# v1.net
KiCad netlist of a schematic drawn in EAGLE
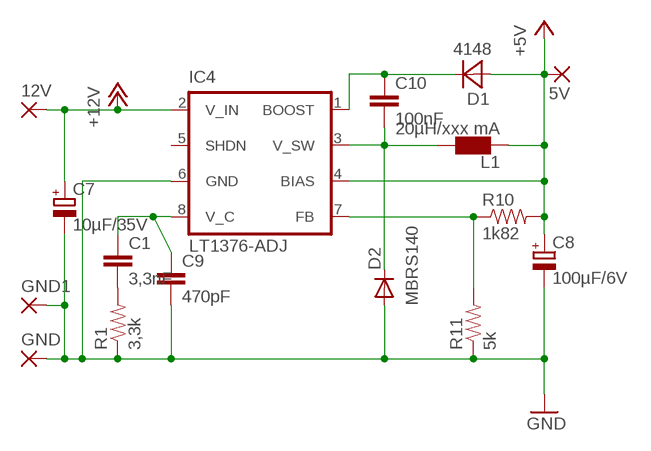
[diagram p0: schematic, sheet 1]
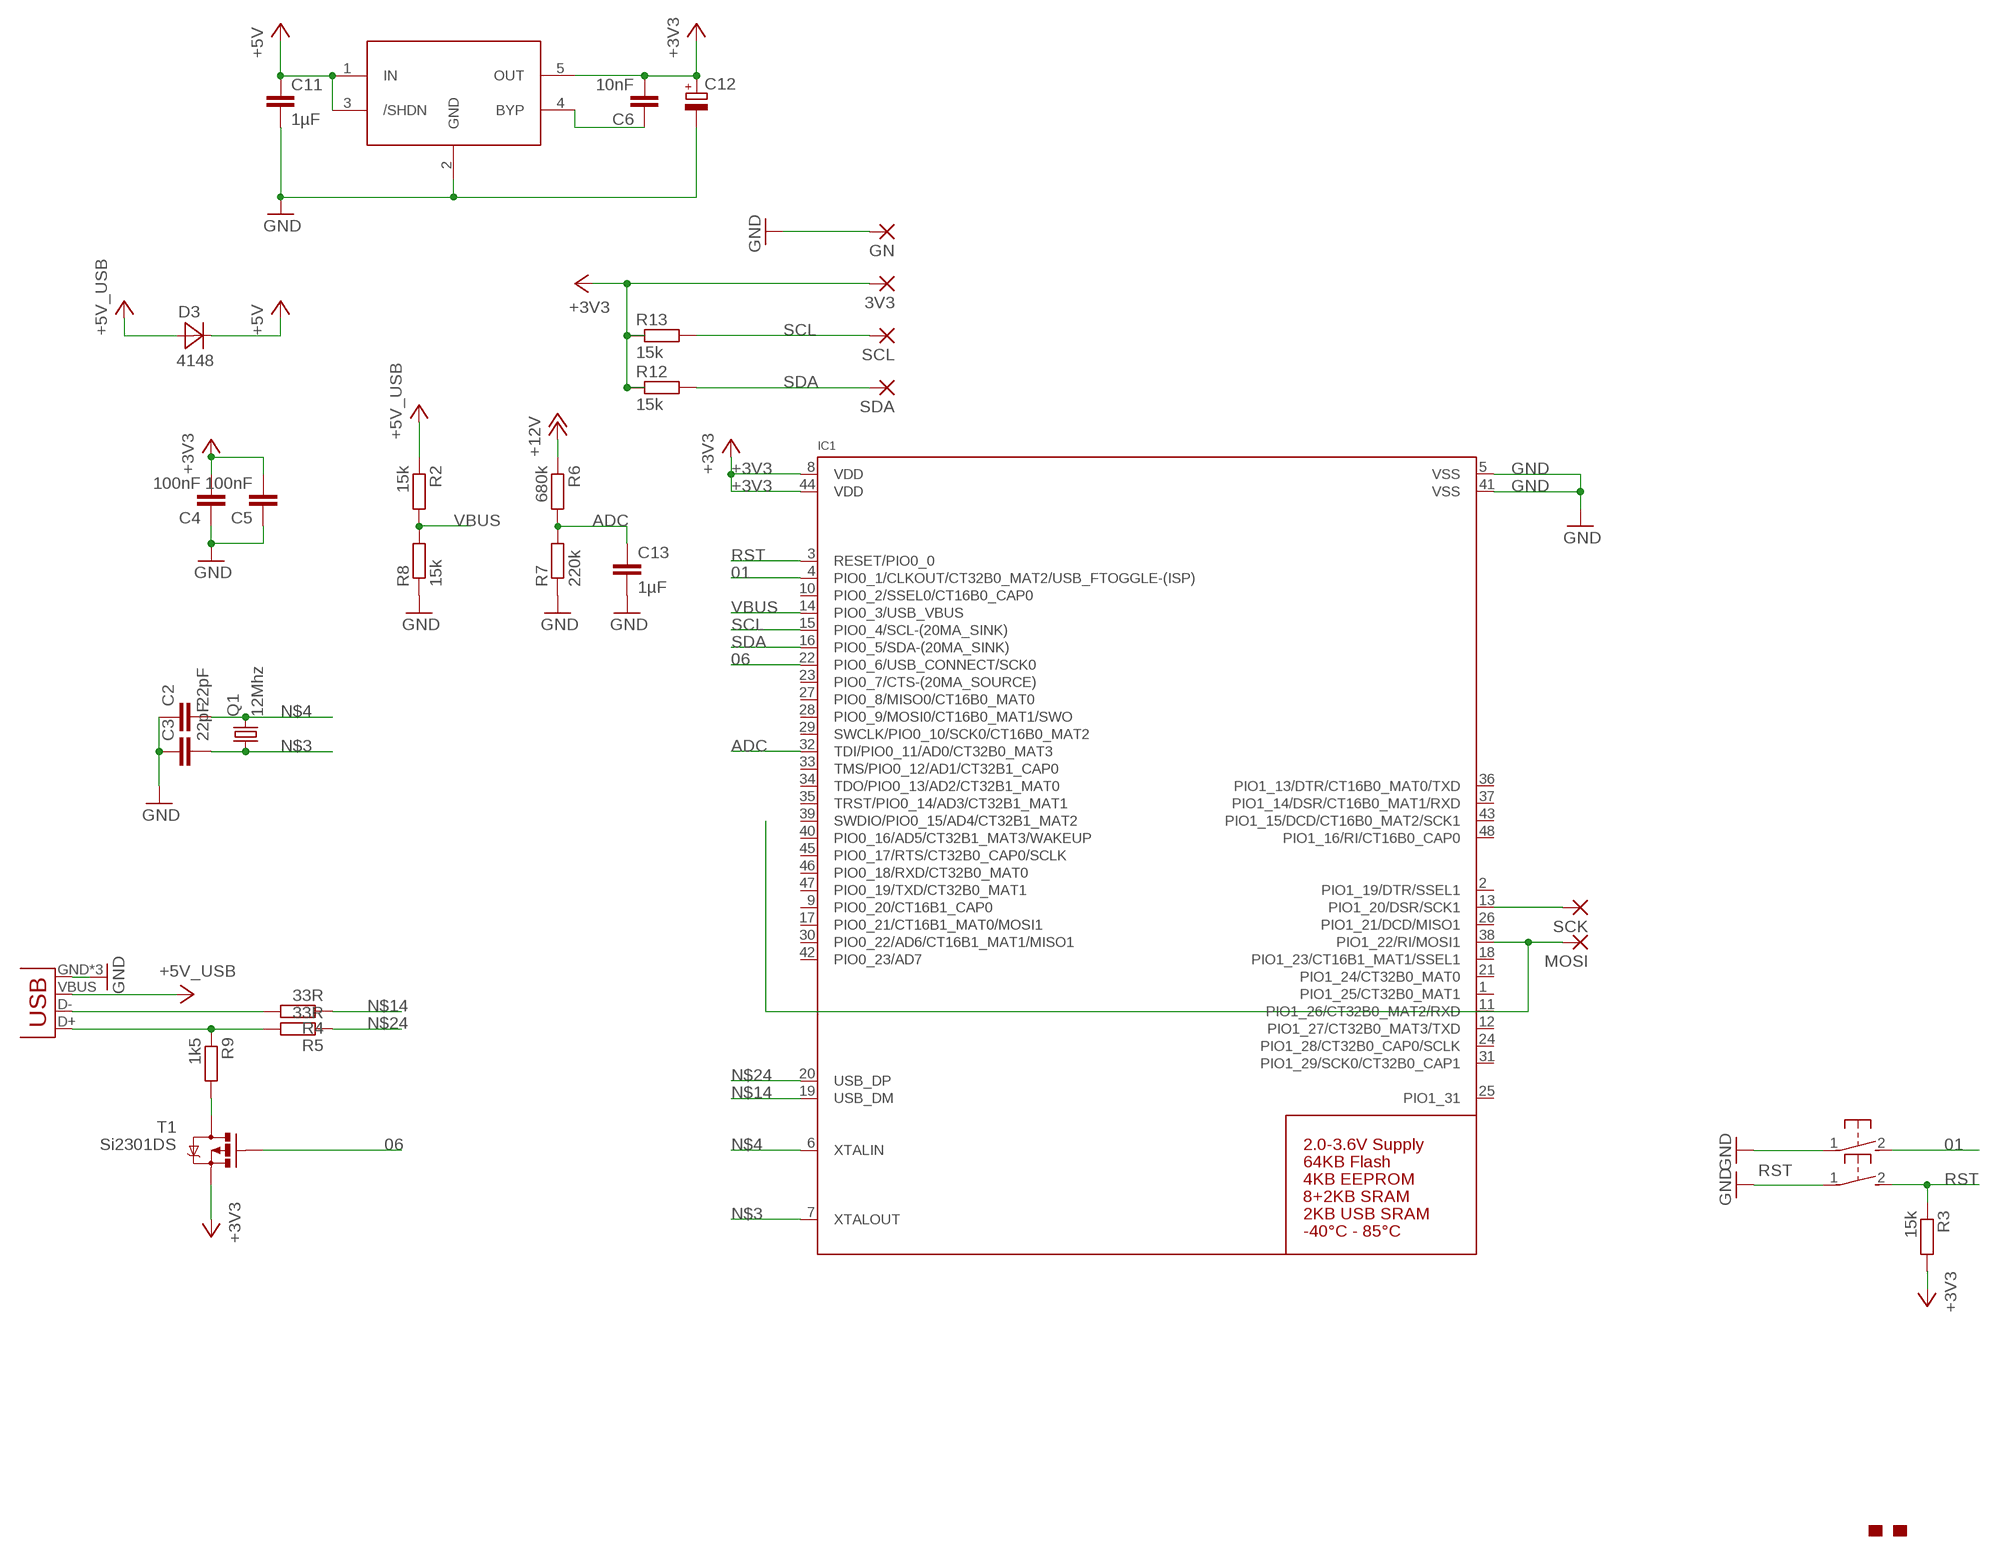
[diagram p1: schematic, sheet 2]

(export (version "E")
  (design (tool "Eeschema 10.0.6"))
  (components
    (comp (ref "3V3")
      (value "SMD2")
      (footprint "eagle-import:SMD1,27-2,54")
      (libsource (lib "eagle-import") (part "SMD2"))
    )
    (comp (ref "BL")
      (value "SWITCH_MCTAEF")
      (footprint "eagle-import:SWITCH_MCTAEF")
      (libsource (lib "eagle-import") (part "SWITCH_MCTAEF"))
    )
    (comp (ref "C2")
      (value "22pF")
      (footprint "eagle-import:C0402")
      (libsource (lib "eagle-import") (part "C-EUC0402"))
    )
    (comp (ref "C3")
      (value "22pF")
      (footprint "eagle-import:C0402")
      (libsource (lib "eagle-import") (part "C-EUC0402"))
    )
    (comp (ref "C4")
      (value "100nF")
      (footprint "eagle-import:C0402")
      (libsource (lib "eagle-import") (part "C-EUC0402"))
    )
    (comp (ref "C5")
      (value "100nF")
      (footprint "eagle-import:C0402")
      (libsource (lib "eagle-import") (part "C-EUC0402"))
    )
    (comp (ref "C6")
      (value "10nF")
      (footprint "eagle-import:C0402")
      (libsource (lib "eagle-import") (part "C-EUC0402"))
    )
    (comp (ref "C11")
      (value "1µF")
      (footprint "eagle-import:0805")
      (libsource (lib "eagle-import") (part "SparkFun-Capacitors_CAP0805"))
    )
    (comp (ref "C12")
      (value "CPOL-EUSMCA")
      (footprint "eagle-import:SMC_A")
      (libsource (lib "eagle-import") (part "CPOL-EUSMCA"))
    )
    (comp (ref "C13")
      (value "1µF")
      (footprint "eagle-import:0805")
      (libsource (lib "eagle-import") (part "SparkFun-Capacitors_CAP0805"))
    )
    (comp (ref "D3")
      (value "4148")
      (footprint "eagle-import:DIODE_0805")
      (libsource (lib "eagle-import") (part "DIODE_0805"))
    )
    (comp (ref "GN")
      (value "SMD2")
      (footprint "eagle-import:SMD1,27-2,54")
      (libsource (lib "eagle-import") (part "SMD2"))
    )
    (comp (ref "IC1")
      (value "LPC1347_QFP48")
      (footprint "eagle-import:LQFP48")
      (libsource (lib "eagle-import") (part "LPC1347_QFP48"))
    )
    (comp (ref "IC2")
      (value "LT1761")
      (footprint "eagle-import:SOT23-5L")
      (libsource (lib "eagle-import") (part "LT1761"))
    )
    (comp (ref "MOSI")
      (value "SMD5")
      (footprint "eagle-import:SMD2,54-5,08")
      (libsource (lib "eagle-import") (part "SMD5"))
    )
    (comp (ref "Q1")
      (value "12Mhz")
      (footprint "eagle-import:MT")
      (libsource (lib "eagle-import") (part "MT-OSCILLATOR"))
    )
    (comp (ref "R2")
      (value "15k")
      (footprint "eagle-import:R0402")
      (libsource (lib "eagle-import") (part "R-EU_R0402"))
    )
    (comp (ref "R3")
      (value "15k")
      (footprint "eagle-import:R0402")
      (libsource (lib "eagle-import") (part "R-EU_R0402"))
    )
    (comp (ref "R4")
      (value "33R")
      (footprint "eagle-import:R0402")
      (libsource (lib "eagle-import") (part "R-EU_R0402"))
    )
    (comp (ref "R5")
      (value "33R")
      (footprint "eagle-import:R0402")
      (libsource (lib "eagle-import") (part "R-EU_R0402"))
    )
    (comp (ref "R6")
      (value "680k")
      (footprint "eagle-import:R0402")
      (libsource (lib "eagle-import") (part "R-EU_R0402"))
    )
    (comp (ref "R7")
      (value "220k")
      (footprint "eagle-import:R0402")
      (libsource (lib "eagle-import") (part "R-EU_R0402"))
    )
    (comp (ref "R8")
      (value "15k")
      (footprint "eagle-import:R0402")
      (libsource (lib "eagle-import") (part "R-EU_R0402"))
    )
    (comp (ref "R9")
      (value "1k5")
      (footprint "eagle-import:R0402")
      (libsource (lib "eagle-import") (part "R-EU_R0402"))
    )
    (comp (ref "R12")
      (value "15k")
      (footprint "eagle-import:R0402")
      (libsource (lib "eagle-import") (part "R-EU_R0402"))
    )
    (comp (ref "R13")
      (value "15k")
      (footprint "eagle-import:R0402")
      (libsource (lib "eagle-import") (part "R-EU_R0402"))
    )
    (comp (ref "RST")
      (value "SWITCH_MCTAEF")
      (footprint "eagle-import:SWITCH_MCTAEF")
      (libsource (lib "eagle-import") (part "SWITCH_MCTAEF"))
    )
    (comp (ref "SCK")
      (value "SMD5")
      (footprint "eagle-import:SMD2,54-5,08")
      (libsource (lib "eagle-import") (part "SMD5"))
    )
    (comp (ref "SCL")
      (value "SMD2")
      (footprint "eagle-import:SMD1,27-2,54")
      (libsource (lib "eagle-import") (part "SMD2"))
    )
    (comp (ref "SDA")
      (value "SMD2")
      (footprint "eagle-import:SMD1,27-2,54")
      (libsource (lib "eagle-import") (part "SMD2"))
    )
    (comp (ref "T1")
      (value "Si2301DS")
      (footprint "eagle-import:SOT23")
      (libsource (lib "eagle-import") (part "MOSFET-PCHANNEL"))
    )
    (comp (ref "U$1")
      (value "MAKE-DD_LOGO'PROMPT'")
      (footprint "eagle-import:MAKE-DD_LOGO_PROMPT")
      (libsource (lib "eagle-import") (part "MAKE-DD_LOGO'PROMPT'"))
    )
    (comp (ref "X1")
      (value "USB-MICROB")
      (footprint "eagle-import:USB-MICROB")
      (libsource (lib "eagle-import") (part "USB-MICROB"))
    )
    (comp (ref "5V")
      (value "SMD5")
      (footprint "eagle-import:SMD2,54-5,08")
      (libsource (lib "eagle-import") (part "SMD5"))
    )
    (comp (ref "12V")
      (value "SMD5")
      (footprint "eagle-import:SMD2,54-5,08")
      (libsource (lib "eagle-import") (part "SMD5"))
    )
    (comp (ref "C1")
      (value "3,3nF")
      (footprint "eagle-import:0805")
      (libsource (lib "eagle-import") (part "CAP0805"))
    )
    (comp (ref "C7")
      (value "10µF/35V")
      (footprint "eagle-import:SMC_D")
      (libsource (lib "eagle-import") (part "resistor_CPOL-EUSMCD"))
    )
    (comp (ref "C8")
      (value "100µF/6V")
      (footprint "eagle-import:SMC_D")
      (libsource (lib "eagle-import") (part "resistor_CPOL-EUSMCD"))
    )
    (comp (ref "C9")
      (value "470pF")
      (footprint "eagle-import:0805")
      (libsource (lib "eagle-import") (part "CAP0805"))
    )
    (comp (ref "C10")
      (value "100nF")
      (footprint "eagle-import:0805")
      (libsource (lib "eagle-import") (part "CAP0805"))
    )
    (comp (ref "D1")
      (value "4148")
      (footprint "eagle-import:DIODE_0805")
      (libsource (lib "eagle-import") (part "DIODE_0805"))
    )
    (comp (ref "D2")
      (value "MBRS140")
      (footprint "eagle-import:SMB")
      (libsource (lib "eagle-import") (part "DIODE-SMB"))
    )
    (comp (ref "GND")
      (value "SMD5")
      (footprint "eagle-import:SMD2,54-5,08")
      (libsource (lib "eagle-import") (part "SMD5"))
    )
    (comp (ref "GND1")
      (value "SMD5")
      (footprint "eagle-import:SMD2,54-5,08")
      (libsource (lib "eagle-import") (part "SMD5"))
    )
    (comp (ref "IC4")
      (value "LT1376-ADJ")
      (footprint "eagle-import:SO-08")
      (libsource (lib "eagle-import") (part "LT1376"))
    )
    (comp (ref "L1")
      (value "20µH/xxx mA")
      (footprint "eagle-import:PIS2408")
      (libsource (lib "eagle-import") (part "PIS2408"))
    )
    (comp (ref "R1")
      (value "3,3k")
      (footprint "eagle-import:0805")
      (libsource (lib "eagle-import") (part "RESISTOR"))
    )
    (comp (ref "R10")
      (value "1k82")
      (footprint "eagle-import:0805")
      (libsource (lib "eagle-import") (part "RESISTOR"))
    )
    (comp (ref "R11")
      (value "5k")
      (footprint "eagle-import:0805")
      (libsource (lib "eagle-import") (part "RESISTOR"))
    )
  )
  (nets
    (net (code "1") (name "+3V3") (class "Default")
      (node (ref "3V3") (pin "1") (pinfunction "P_1") (pintype "passive"))
      (node (ref "C12") (pin "+") (pinfunction "+_+") (pintype "passive"))
      (node (ref "C4") (pin "2") (pinfunction "2_2") (pintype "passive"))
      (node (ref "C5") (pin "2") (pinfunction "2_2") (pintype "passive"))
      (node (ref "C6") (pin "2") (pinfunction "2_2") (pintype "passive"))
      (node (ref "IC1") (pin "44") (pinfunction "VDD_44") (pintype "power_in"))
      (node (ref "IC1") (pin "8") (pinfunction "VDD_8") (pintype "power_in"))
      (node (ref "IC2") (pin "5") (pinfunction "OUT_5") (pintype "bidirectional"))
      (node (ref "R12") (pin "1") (pinfunction "1_1") (pintype "passive"))
      (node (ref "R13") (pin "1") (pinfunction "1_1") (pintype "passive"))
      (node (ref "R3") (pin "2") (pinfunction "2_2") (pintype "passive"))
      (node (ref "T1") (pin "2") (pinfunction "S_2") (pintype "passive"))
    )
    (net (code "2") (name "+5V") (class "Default")
      (node (ref "5V") (pin "1") (pinfunction "P_1") (pintype "passive"))
      (node (ref "C11") (pin "1") (pinfunction "1_1") (pintype "passive"))
      (node (ref "C8") (pin "+") (pinfunction "+_+") (pintype "passive"))
      (node (ref "D1") (pin "2") (pinfunction "A_2") (pintype "passive"))
      (node (ref "D3") (pin "1") (pinfunction "C_1") (pintype "passive"))
      (node (ref "IC2") (pin "1") (pinfunction "IN_1") (pintype "bidirectional"))
      (node (ref "IC2") (pin "3") (pinfunction "/SHDN_3") (pintype "bidirectional"))
      (node (ref "IC4") (pin "4") (pinfunction "BIAS_4") (pintype "output"))
      (node (ref "L1") (pin "P$2") (pinfunction "2_P$2") (pintype "passive"))
      (node (ref "R10") (pin "2") (pinfunction "2_2") (pintype "passive"))
    )
    (net (code "3") (name "+5V_USB") (class "Default")
      (node (ref "D3") (pin "2") (pinfunction "A_2") (pintype "passive"))
      (node (ref "R2") (pin "1") (pinfunction "1_1") (pintype "passive"))
      (node (ref "X1") (pin "VBUS") (pinfunction "VBUS_VBUS") (pintype "bidirectional"))
    )
    (net (code "4") (name "+12V") (class "Default")
      (node (ref "12V") (pin "1") (pinfunction "P_1") (pintype "passive"))
      (node (ref "C7") (pin "+") (pinfunction "+_+") (pintype "passive"))
      (node (ref "IC4") (pin "2") (pinfunction "V_IN_2") (pintype "passive"))
      (node (ref "R6") (pin "1") (pinfunction "1_1") (pintype "passive"))
    )
    (net (code "5") (name "01") (class "Default")
      (node (ref "BL") (pin "2") (pinfunction "2_2") (pintype "passive"))
      (node (ref "IC1") (pin "4") (pinfunction "PIO0_1/CLKOUT/CT32B0_MAT2/USB_FTOGGLE-(ISP)_4") (pintype "bidirectional"))
    )
    (net (code "6") (name "06") (class "Default")
      (node (ref "IC1") (pin "22") (pinfunction "PIO0_6/USB_CONNECT/SCK0_22") (pintype "bidirectional"))
      (node (ref "T1") (pin "1") (pinfunction "G_1") (pintype "passive"))
    )
    (net (code "7") (name "ADC") (class "Default")
      (node (ref "C13") (pin "1") (pinfunction "1_1") (pintype "passive"))
      (node (ref "IC1") (pin "32") (pinfunction "TDI/PIO0_11/AD0/CT32B0_MAT3_32") (pintype "bidirectional"))
      (node (ref "R6") (pin "2") (pinfunction "2_2") (pintype "passive"))
      (node (ref "R7") (pin "2") (pinfunction "2_2") (pintype "passive"))
    )
    (net (code "8") (name "GND") (class "Default")
      (node (ref "BL") (pin "1") (pinfunction "1_1") (pintype "passive"))
      (node (ref "C11") (pin "2") (pinfunction "2_2") (pintype "passive"))
      (node (ref "C12") (pin "-") (pinfunction "-_-") (pintype "passive"))
      (node (ref "C13") (pin "2") (pinfunction "2_2") (pintype "passive"))
      (node (ref "C2") (pin "1") (pinfunction "1_1") (pintype "passive"))
      (node (ref "C3") (pin "1") (pinfunction "1_1") (pintype "passive"))
      (node (ref "C4") (pin "1") (pinfunction "1_1") (pintype "passive"))
      (node (ref "C5") (pin "1") (pinfunction "1_1") (pintype "passive"))
      (node (ref "C7") (pin "-") (pinfunction "-_-") (pintype "passive"))
      (node (ref "C8") (pin "-") (pinfunction "-_-") (pintype "passive"))
      (node (ref "C9") (pin "2") (pinfunction "2_2") (pintype "passive"))
      (node (ref "D2") (pin "A") (pinfunction "A_A") (pintype "passive"))
      (node (ref "GN") (pin "1") (pinfunction "P_1") (pintype "passive"))
      (node (ref "GND") (pin "1") (pinfunction "P_1") (pintype "passive"))
      (node (ref "GND1") (pin "1") (pinfunction "P_1") (pintype "passive"))
      (node (ref "IC1") (pin "41") (pinfunction "VSS_41") (pintype "power_in"))
      (node (ref "IC1") (pin "5") (pinfunction "VSS_5") (pintype "power_in"))
      (node (ref "IC2") (pin "2") (pinfunction "GND_2") (pintype "bidirectional"))
      (node (ref "IC4") (pin "6") (pinfunction "GND_6") (pintype "power_in"))
      (node (ref "R1") (pin "1") (pinfunction "1_1") (pintype "passive"))
      (node (ref "R11") (pin "1") (pinfunction "1_1") (pintype "passive"))
      (node (ref "R7") (pin "1") (pinfunction "1_1") (pintype "passive"))
      (node (ref "R8") (pin "1") (pinfunction "1_1") (pintype "passive"))
      (node (ref "RST") (pin "1") (pinfunction "1_1") (pintype "passive"))
      (node (ref "X1") (pin "GND") (pinfunction "GND_GND") (pintype "bidirectional"))
      (node (ref "X1") (pin "MT1") (pinfunction "GND_MT1") (pintype "bidirectional"))
      (node (ref "X1") (pin "MT2") (pinfunction "GND_MT2") (pintype "bidirectional"))
    )
    (net (code "9") (name "N$3") (class "Default")
      (node (ref "C3") (pin "2") (pinfunction "2_2") (pintype "passive"))
      (node (ref "IC1") (pin "7") (pinfunction "XTALOUT_7") (pintype "bidirectional"))
      (node (ref "Q1") (pin "1") (pinfunction "1_1") (pintype "passive"))
    )
    (net (code "10") (name "N$4") (class "Default")
      (node (ref "C2") (pin "2") (pinfunction "2_2") (pintype "passive"))
      (node (ref "IC1") (pin "6") (pinfunction "XTALIN_6") (pintype "bidirectional"))
      (node (ref "Q1") (pin "3") (pinfunction "2_3") (pintype "passive"))
    )
    (net (code "11") (name "N$14") (class "Default")
      (node (ref "IC1") (pin "19") (pinfunction "USB_DM_19") (pintype "bidirectional"))
      (node (ref "R4") (pin "1") (pinfunction "1_1") (pintype "passive"))
    )
    (net (code "12") (name "N$24") (class "Default")
      (node (ref "IC1") (pin "20") (pinfunction "USB_DP_20") (pintype "bidirectional"))
      (node (ref "R5") (pin "1") (pinfunction "1_1") (pintype "passive"))
    )
    (net (code "13") (name "Net-(C1-Pad2)") (class "Default")
      (node (ref "C1") (pin "2") (pinfunction "2_2") (pintype "passive"))
      (node (ref "R1") (pin "2") (pinfunction "2_2") (pintype "passive"))
    )
    (net (code "14") (name "Net-(D1-C)") (class "Default")
      (node (ref "C10") (pin "1") (pinfunction "1_1") (pintype "passive"))
      (node (ref "D1") (pin "1") (pinfunction "C_1") (pintype "passive"))
      (node (ref "IC4") (pin "1") (pinfunction "BOOST_1") (pintype "passive"))
    )
    (net (code "15") (name "Net-(IC1-PIO1_20{slash}DSR{slash}SCK1)") (class "Default")
      (node (ref "IC1") (pin "13") (pinfunction "PIO1_20/DSR/SCK1_13") (pintype "bidirectional"))
      (node (ref "SCK") (pin "1") (pinfunction "P_1") (pintype "passive"))
    )
    (net (code "16") (name "Net-(IC1-PIO1_22{slash}RI{slash}MOSI1)") (class "Default")
      (node (ref "IC1") (pin "38") (pinfunction "PIO1_22/RI/MOSI1_38") (pintype "bidirectional"))
      (node (ref "MOSI") (pin "1") (pinfunction "P_1") (pintype "passive"))
    )
    (net (code "17") (name "Net-(IC2-BYP)") (class "Default")
      (node (ref "C6") (pin "1") (pinfunction "1_1") (pintype "passive"))
      (node (ref "IC2") (pin "4") (pinfunction "BYP_4") (pintype "bidirectional"))
    )
    (net (code "18") (name "Net-(IC4-FB)") (class "Default")
      (node (ref "IC4") (pin "7") (pinfunction "FB_7") (pintype "passive"))
      (node (ref "R10") (pin "1") (pinfunction "1_1") (pintype "passive"))
      (node (ref "R11") (pin "2") (pinfunction "2_2") (pintype "passive"))
    )
    (net (code "19") (name "Net-(IC4-V_C)") (class "Default")
      (node (ref "C1") (pin "1") (pinfunction "1_1") (pintype "passive"))
      (node (ref "C9") (pin "1") (pinfunction "1_1") (pintype "passive"))
      (node (ref "IC4") (pin "8") (pinfunction "V_C_8") (pintype "input"))
    )
    (net (code "20") (name "Net-(IC4-V_SW)") (class "Default")
      (node (ref "C10") (pin "2") (pinfunction "2_2") (pintype "passive"))
      (node (ref "D2") (pin "C") (pinfunction "C_C") (pintype "passive"))
      (node (ref "IC4") (pin "3") (pinfunction "V_SW_3") (pintype "power_in"))
      (node (ref "L1") (pin "P$1") (pinfunction "1_P$1") (pintype "passive"))
    )
    (net (code "21") (name "Net-(R4-Pad2)") (class "Default")
      (node (ref "R4") (pin "2") (pinfunction "2_2") (pintype "passive"))
      (node (ref "X1") (pin "D-") (pinfunction "D-_D-") (pintype "bidirectional"))
    )
    (net (code "22") (name "Net-(R5-Pad2)") (class "Default")
      (node (ref "R5") (pin "2") (pinfunction "2_2") (pintype "passive"))
      (node (ref "R9") (pin "1") (pinfunction "1_1") (pintype "passive"))
      (node (ref "X1") (pin "D+") (pinfunction "D+_D+") (pintype "bidirectional"))
    )
    (net (code "23") (name "Net-(T1-D)") (class "Default")
      (node (ref "R9") (pin "2") (pinfunction "2_2") (pintype "passive"))
      (node (ref "T1") (pin "3") (pinfunction "D_3") (pintype "passive"))
    )
    (net (code "24") (name "RST") (class "Default")
      (node (ref "IC1") (pin "3") (pinfunction "RESET/PIO0_0_3") (pintype "bidirectional"))
      (node (ref "R3") (pin "1") (pinfunction "1_1") (pintype "passive"))
      (node (ref "RST") (pin "2") (pinfunction "2_2") (pintype "passive"))
    )
    (net (code "25") (name "SCL") (class "Default")
      (node (ref "IC1") (pin "15") (pinfunction "PIO0_4/SCL-(20MA_SINK)_15") (pintype "bidirectional"))
      (node (ref "R13") (pin "2") (pinfunction "2_2") (pintype "passive"))
      (node (ref "SCL") (pin "1") (pinfunction "P_1") (pintype "passive"))
    )
    (net (code "26") (name "SDA") (class "Default")
      (node (ref "IC1") (pin "16") (pinfunction "PIO0_5/SDA-(20MA_SINK)_16") (pintype "bidirectional"))
      (node (ref "R12") (pin "2") (pinfunction "2_2") (pintype "passive"))
      (node (ref "SDA") (pin "1") (pinfunction "P_1") (pintype "passive"))
    )
    (net (code "27") (name "VBUS") (class "Default")
      (node (ref "IC1") (pin "14") (pinfunction "PIO0_3/USB_VBUS_14") (pintype "bidirectional"))
      (node (ref "R2") (pin "2") (pinfunction "2_2") (pintype "passive"))
      (node (ref "R8") (pin "2") (pinfunction "2_2") (pintype "passive"))
    )
    (net (code "28") (name "unconnected-(IC1-PIO0_2{slash}SSEL0{slash}CT16B0_CAP0-Pad10)") (class "Default")
      (node (ref "IC1") (pin "10") (pinfunction "PIO0_2/SSEL0/CT16B0_CAP0_10") (pintype "bidirectional"))
    )
    (net (code "29") (name "unconnected-(IC1-PIO0_7{slash}CTS-(20MA_SOURCE)-Pad23)") (class "Default")
      (node (ref "IC1") (pin "23") (pinfunction "PIO0_7/CTS-(20MA_SOURCE)_23") (pintype "bidirectional"))
    )
    (net (code "30") (name "unconnected-(IC1-PIO0_8{slash}MISO0{slash}CT16B0_MAT0-Pad27)") (class "Default")
      (node (ref "IC1") (pin "27") (pinfunction "PIO0_8/MISO0/CT16B0_MAT0_27") (pintype "bidirectional"))
    )
    (net (code "31") (name "unconnected-(IC1-PIO0_9{slash}MOSI0{slash}CT16B0_MAT1{slash}SWO-Pad28)") (class "Default")
      (node (ref "IC1") (pin "28") (pinfunction "PIO0_9/MOSI0/CT16B0_MAT1/SWO_28") (pintype "bidirectional"))
    )
    (net (code "32") (name "unconnected-(IC1-PIO0_16{slash}AD5{slash}CT32B1_MAT3{slash}WAKEUP-Pad40)") (class "Default")
      (node (ref "IC1") (pin "40") (pinfunction "PIO0_16/AD5/CT32B1_MAT3/WAKEUP_40") (pintype "bidirectional"))
    )
    (net (code "33") (name "unconnected-(IC1-PIO0_17{slash}RTS{slash}CT32B0_CAP0{slash}SCLK-Pad45)") (class "Default")
      (node (ref "IC1") (pin "45") (pinfunction "PIO0_17/RTS/CT32B0_CAP0/SCLK_45") (pintype "bidirectional"))
    )
    (net (code "34") (name "unconnected-(IC1-PIO0_18{slash}RXD{slash}CT32B0_MAT0-Pad46)") (class "Default")
      (node (ref "IC1") (pin "46") (pinfunction "PIO0_18/RXD/CT32B0_MAT0_46") (pintype "bidirectional"))
    )
    (net (code "35") (name "unconnected-(IC1-PIO0_19{slash}TXD{slash}CT32B0_MAT1-Pad47)") (class "Default")
      (node (ref "IC1") (pin "47") (pinfunction "PIO0_19/TXD/CT32B0_MAT1_47") (pintype "bidirectional"))
    )
    (net (code "36") (name "unconnected-(IC1-PIO0_20{slash}CT16B1_CAP0-Pad9)") (class "Default")
      (node (ref "IC1") (pin "9") (pinfunction "PIO0_20/CT16B1_CAP0_9") (pintype "bidirectional"))
    )
    (net (code "37") (name "unconnected-(IC1-PIO0_21{slash}CT16B1_MAT0{slash}MOSI1-Pad17)") (class "Default")
      (node (ref "IC1") (pin "17") (pinfunction "PIO0_21/CT16B1_MAT0/MOSI1_17") (pintype "bidirectional"))
    )
    (net (code "38") (name "unconnected-(IC1-PIO0_22{slash}AD6{slash}CT16B1_MAT1{slash}MISO1-Pad30)") (class "Default")
      (node (ref "IC1") (pin "30") (pinfunction "PIO0_22/AD6/CT16B1_MAT1/MISO1_30") (pintype "bidirectional"))
    )
    (net (code "39") (name "unconnected-(IC1-PIO0_23{slash}AD7-Pad42)") (class "Default")
      (node (ref "IC1") (pin "42") (pinfunction "PIO0_23/AD7_42") (pintype "bidirectional"))
    )
    (net (code "40") (name "unconnected-(IC1-PIO1_13{slash}DTR{slash}CT16B0_MAT0{slash}TXD-Pad36)") (class "Default")
      (node (ref "IC1") (pin "36") (pinfunction "PIO1_13/DTR/CT16B0_MAT0/TXD_36") (pintype "bidirectional"))
    )
    (net (code "41") (name "unconnected-(IC1-PIO1_14{slash}DSR{slash}CT16B0_MAT1{slash}RXD-Pad37)") (class "Default")
      (node (ref "IC1") (pin "37") (pinfunction "PIO1_14/DSR/CT16B0_MAT1/RXD_37") (pintype "bidirectional"))
    )
    (net (code "42") (name "unconnected-(IC1-PIO1_15{slash}DCD{slash}CT16B0_MAT2{slash}SCK1-Pad43)") (class "Default")
      (node (ref "IC1") (pin "43") (pinfunction "PIO1_15/DCD/CT16B0_MAT2/SCK1_43") (pintype "bidirectional"))
    )
    (net (code "43") (name "unconnected-(IC1-PIO1_16{slash}RI{slash}CT16B0_CAP0-Pad48)") (class "Default")
      (node (ref "IC1") (pin "48") (pinfunction "PIO1_16/RI/CT16B0_CAP0_48") (pintype "bidirectional"))
    )
    (net (code "44") (name "unconnected-(IC1-PIO1_19{slash}DTR{slash}SSEL1-Pad2)") (class "Default")
      (node (ref "IC1") (pin "2") (pinfunction "PIO1_19/DTR/SSEL1_2") (pintype "bidirectional"))
    )
    (net (code "45") (name "unconnected-(IC1-PIO1_21{slash}DCD{slash}MISO1-Pad26)") (class "Default")
      (node (ref "IC1") (pin "26") (pinfunction "PIO1_21/DCD/MISO1_26") (pintype "bidirectional"))
    )
    (net (code "46") (name "unconnected-(IC1-PIO1_23{slash}CT16B1_MAT1{slash}SSEL1-Pad18)") (class "Default")
      (node (ref "IC1") (pin "18") (pinfunction "PIO1_23/CT16B1_MAT1/SSEL1_18") (pintype "bidirectional"))
    )
    (net (code "47") (name "unconnected-(IC1-PIO1_24{slash}CT32B0_MAT0-Pad21)") (class "Default")
      (node (ref "IC1") (pin "21") (pinfunction "PIO1_24/CT32B0_MAT0_21") (pintype "bidirectional"))
    )
    (net (code "48") (name "unconnected-(IC1-PIO1_25{slash}CT32B0_MAT1-Pad1)") (class "Default")
      (node (ref "IC1") (pin "1") (pinfunction "PIO1_25/CT32B0_MAT1_1") (pintype "bidirectional"))
    )
    (net (code "49") (name "unconnected-(IC1-PIO1_26{slash}CT32B0_MAT2{slash}RXD-Pad11)") (class "Default")
      (node (ref "IC1") (pin "11") (pinfunction "PIO1_26/CT32B0_MAT2/RXD_11") (pintype "bidirectional"))
    )
    (net (code "50") (name "unconnected-(IC1-PIO1_27{slash}CT32B0_MAT3{slash}TXD-Pad12)") (class "Default")
      (node (ref "IC1") (pin "12") (pinfunction "PIO1_27/CT32B0_MAT3/TXD_12") (pintype "bidirectional"))
    )
    (net (code "51") (name "unconnected-(IC1-PIO1_28{slash}CT32B0_CAP0{slash}SCLK-Pad24)") (class "Default")
      (node (ref "IC1") (pin "24") (pinfunction "PIO1_28/CT32B0_CAP0/SCLK_24") (pintype "bidirectional"))
    )
    (net (code "52") (name "unconnected-(IC1-PIO1_29{slash}SCK0{slash}CT32B0_CAP1-Pad31)") (class "Default")
      (node (ref "IC1") (pin "31") (pinfunction "PIO1_29/SCK0/CT32B0_CAP1_31") (pintype "bidirectional"))
    )
    (net (code "53") (name "unconnected-(IC1-PIO1_31-Pad25)") (class "Default")
      (node (ref "IC1") (pin "25") (pinfunction "PIO1_31_25") (pintype "bidirectional"))
    )
    (net (code "54") (name "unconnected-(IC1-SWCLK{slash}PIO0_10{slash}SCK0{slash}CT16B0_MAT2-Pad29)") (class "Default")
      (node (ref "IC1") (pin "29") (pinfunction "SWCLK/PIO0_10/SCK0/CT16B0_MAT2_29") (pintype "bidirectional"))
    )
    (net (code "55") (name "unconnected-(IC1-SWDIO{slash}PIO0_15{slash}AD4{slash}CT32B1_MAT2-Pad39)") (class "Default")
      (node (ref "IC1") (pin "39") (pinfunction "SWDIO/PIO0_15/AD4/CT32B1_MAT2_39") (pintype "bidirectional"))
    )
    (net (code "56") (name "unconnected-(IC1-TDO{slash}PIO0_13{slash}AD2{slash}CT32B1_MAT0-Pad34)") (class "Default")
      (node (ref "IC1") (pin "34") (pinfunction "TDO/PIO0_13/AD2/CT32B1_MAT0_34") (pintype "bidirectional"))
    )
    (net (code "57") (name "unconnected-(IC1-TMS{slash}PIO0_12{slash}AD1{slash}CT32B1_CAP0-Pad33)") (class "Default")
      (node (ref "IC1") (pin "33") (pinfunction "TMS/PIO0_12/AD1/CT32B1_CAP0_33") (pintype "bidirectional"))
    )
    (net (code "58") (name "unconnected-(IC1-TRST{slash}PIO0_14{slash}AD3{slash}CT32B1_MAT1-Pad35)") (class "Default")
      (node (ref "IC1") (pin "35") (pinfunction "TRST/PIO0_14/AD3/CT32B1_MAT1_35") (pintype "bidirectional"))
    )
    (net (code "59") (name "unconnected-(IC4-SHDN-Pad5)") (class "Default")
      (node (ref "IC4") (pin "5") (pinfunction "SHDN_5") (pintype "input"))
    )
  )
)
